# heartEM.net
KiCad netlist of a schematic drawn in EAGLE
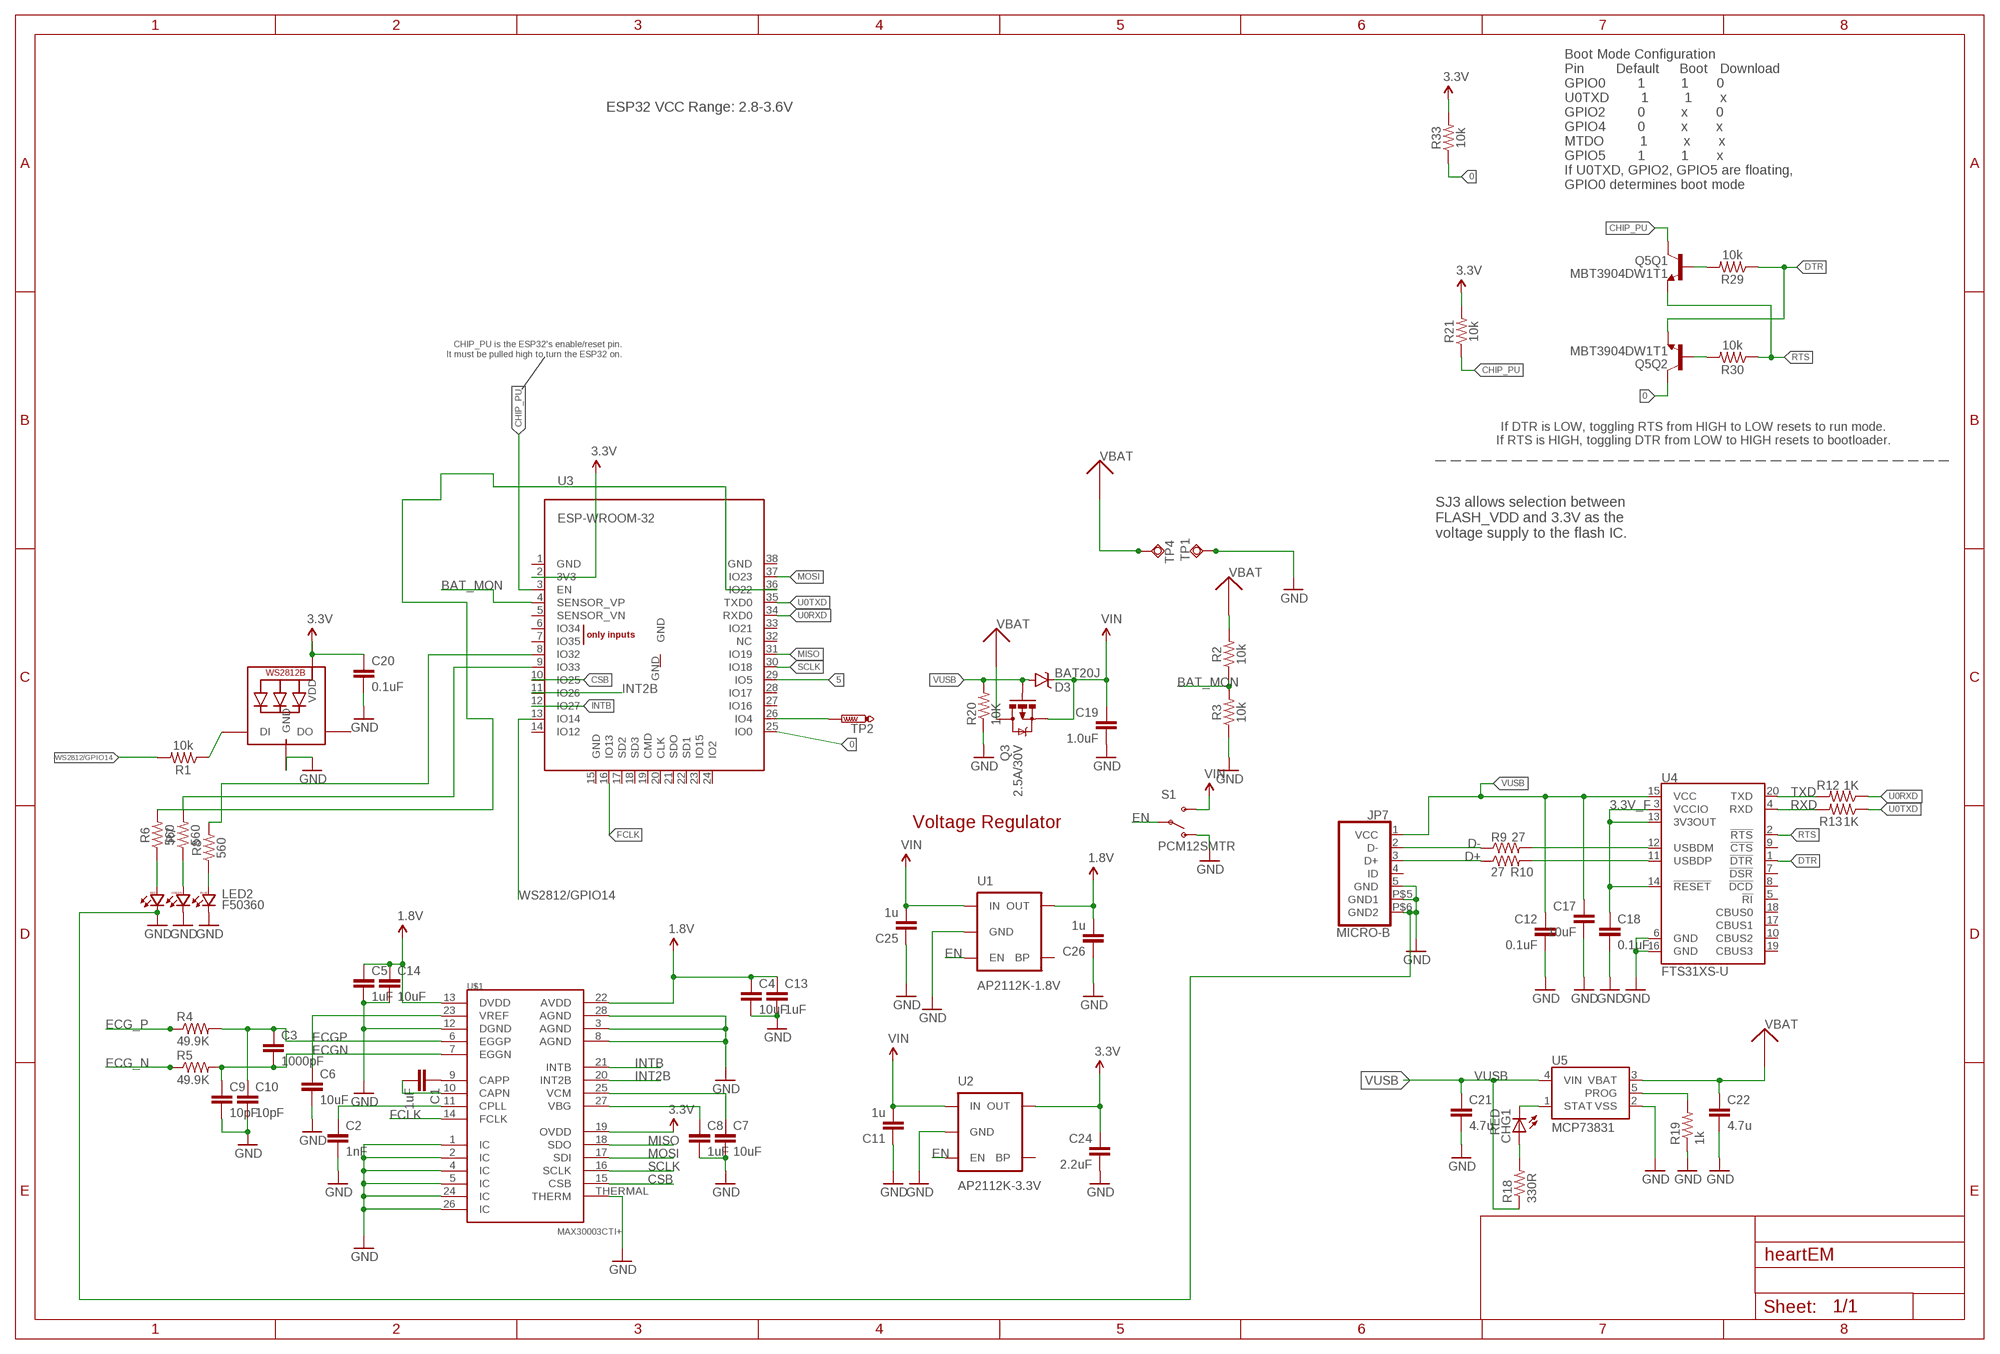
[diagram p0: schematic, sheet 1]

(export (version "E")
  (design (tool "Eeschema 10.0.6"))
  (components
    (comp (ref "C1")
      (value "1uF")
      (footprint "eagle-import:C0603")
      (libsource (lib "eagle-import") (part "C-EUC0603"))
    )
    (comp (ref "C2")
      (value "1nF")
      (footprint "eagle-import:C0603")
      (libsource (lib "eagle-import") (part "C-EUC0603"))
    )
    (comp (ref "C3")
      (value "1000pF")
      (footprint "eagle-import:C0402")
      (libsource (lib "eagle-import") (part "C-EUC0402"))
    )
    (comp (ref "C4")
      (value "10uF")
      (footprint "eagle-import:C0805")
      (libsource (lib "eagle-import") (part "C-EUC0805"))
    )
    (comp (ref "C5")
      (value "1uF")
      (footprint "eagle-import:C0402")
      (libsource (lib "eagle-import") (part "C-EUC0402"))
    )
    (comp (ref "C6")
      (value "10uF")
      (footprint "eagle-import:C0805")
      (libsource (lib "eagle-import") (part "C-EUC0805"))
    )
    (comp (ref "C7")
      (value "10uF")
      (footprint "eagle-import:C0805")
      (libsource (lib "eagle-import") (part "C-EUC0805"))
    )
    (comp (ref "C8")
      (value "1uF")
      (footprint "eagle-import:C0805")
      (libsource (lib "eagle-import") (part "C-EUC0805"))
    )
    (comp (ref "C9")
      (value "10pF")
      (footprint "eagle-import:C0402")
      (libsource (lib "eagle-import") (part "C-EUC0402"))
    )
    (comp (ref "C10")
      (value "10pF")
      (footprint "eagle-import:C0402")
      (libsource (lib "eagle-import") (part "C-EUC0402"))
    )
    (comp (ref "C11")
      (value "1u")
      (footprint "eagle-import:C0402")
      (libsource (lib "eagle-import") (part "C-EUC0402"))
    )
    (comp (ref "C12")
      (value "0.1uF")
      (footprint "eagle-import:C0402")
      (libsource (lib "eagle-import") (part "C-EUC0402"))
    )
    (comp (ref "C13")
      (value "1uF")
      (footprint "eagle-import:C0805")
      (libsource (lib "eagle-import") (part "C-EUC0805"))
    )
    (comp (ref "C14")
      (value "10uF")
      (footprint "eagle-import:C0603")
      (libsource (lib "eagle-import") (part "C-EUC0603"))
    )
    (comp (ref "C17")
      (value "10uF")
      (footprint "eagle-import:C0805")
      (libsource (lib "eagle-import") (part "C-EUC0805"))
    )
    (comp (ref "C18")
      (value "0.1uF")
      (footprint "eagle-import:C0402")
      (libsource (lib "eagle-import") (part "C-EUC0402"))
    )
    (comp (ref "C19")
      (value "1.0uF")
      (footprint "eagle-import:C0402")
      (libsource (lib "eagle-import") (part "C-EUC0402"))
    )
    (comp (ref "C20")
      (value "0.1uF")
      (footprint "eagle-import:0603")
      (libsource (lib "eagle-import") (part "0.1UF-0603-25V-(+80/-20%)"))
    )
    (comp (ref "C21")
      (value "4.7u")
      (footprint "eagle-import:C0805")
      (libsource (lib "eagle-import") (part "C-EUC0805"))
    )
    (comp (ref "C22")
      (value "4.7u")
      (footprint "eagle-import:C0805")
      (libsource (lib "eagle-import") (part "C-EUC0805"))
    )
    (comp (ref "C24")
      (value "2.2uF")
      (footprint "eagle-import:C0603")
      (libsource (lib "eagle-import") (part "C-EUC0603"))
    )
    (comp (ref "C25")
      (value "1u")
      (footprint "eagle-import:C0402")
      (libsource (lib "eagle-import") (part "C-EUC0402"))
    )
    (comp (ref "C26")
      (value "1u")
      (footprint "eagle-import:C0402")
      (libsource (lib "eagle-import") (part "C-EUC0402"))
    )
    (comp (ref "CHG1")
      (value "RED")
      (footprint "eagle-import:CHIPLED_0603")
      (libsource (lib "eagle-import") (part "LEDCHIPLED_0603"))
    )
    (comp (ref "D3")
      (value "BAT20J")
      (footprint "eagle-import:SOD-323")
      (libsource (lib "eagle-import") (part "DIODE-SCHOTTKY-BAT20J"))
    )
    (comp (ref "JP7")
      (value "MICRO-B")
      (footprint "eagle-import:MICRO-B")
      (libsource (lib "eagle-import") (part "MICRO-B"))
    )
    (comp (ref "LED1")
      (value "WS2812B5050")
      (footprint "eagle-import:WS2812B")
      (libsource (lib "eagle-import") (part "WS2812B5050"))
    )
    (comp (ref "LED2")
      (value "F50360")
      (footprint "eagle-import:F50360")
      (libsource (lib "eagle-import") (part "F50360"))
    )
    (comp (ref "Q3")
      (value "2.5A/30V")
      (footprint "eagle-import:SOT23-3")
      (libsource (lib "eagle-import") (part "MOSFET-PCHANNELDMG2307L"))
    )
    (comp (ref "Q5")
      (value "MBT3904DW1T1")
      (footprint "eagle-import:SC70-6")
      (libsource (lib "eagle-import") (part "MBT3904DW1T1"))
    )
    (comp (ref "R1")
      (value "10k")
      (footprint "eagle-import:0603")
      (libsource (lib "eagle-import") (part "10KOHM-1/10W-1%(0603)0603"))
    )
    (comp (ref "R2")
      (value "10k")
      (footprint "eagle-import:0603")
      (libsource (lib "eagle-import") (part "10KOHM-1/10W-1%(0603)0603"))
    )
    (comp (ref "R3")
      (value "10k")
      (footprint "eagle-import:0603")
      (libsource (lib "eagle-import") (part "10KOHM-1/10W-1%(0603)0603"))
    )
    (comp (ref "R4")
      (value "49.9K")
      (footprint "eagle-import:0805")
      (libsource (lib "eagle-import") (part "RESISTOR0805-RES"))
    )
    (comp (ref "R5")
      (value "49.9K")
      (footprint "eagle-import:0805")
      (libsource (lib "eagle-import") (part "RESISTOR0805-RES"))
    )
    (comp (ref "R6")
      (value "560")
      (footprint "eagle-import:0603")
      (libsource (lib "eagle-import") (part "10KOHM-1/10W-1%(0603)0603"))
    )
    (comp (ref "R7")
      (value "560")
      (footprint "eagle-import:0603")
      (libsource (lib "eagle-import") (part "10KOHM-1/10W-1%(0603)0603"))
    )
    (comp (ref "R8")
      (value "560")
      (footprint "eagle-import:0603")
      (libsource (lib "eagle-import") (part "10KOHM-1/10W-1%(0603)0603"))
    )
    (comp (ref "R9")
      (value "27")
      (footprint "eagle-import:R0402")
      (libsource (lib "eagle-import") (part "R-US_R0402"))
    )
    (comp (ref "R10")
      (value "27")
      (footprint "eagle-import:R0402")
      (libsource (lib "eagle-import") (part "R-US_R0402"))
    )
    (comp (ref "R12")
      (value "1K")
      (footprint "eagle-import:R0402")
      (libsource (lib "eagle-import") (part "R-US_R0402"))
    )
    (comp (ref "R13")
      (value "1K")
      (footprint "eagle-import:R0402")
      (libsource (lib "eagle-import") (part "R-US_R0402"))
    )
    (comp (ref "R18")
      (value "330R")
      (footprint "eagle-import:R0402")
      (libsource (lib "eagle-import") (part "R-US_R0402"))
    )
    (comp (ref "R19")
      (value "1k")
      (footprint "eagle-import:R0402")
      (libsource (lib "eagle-import") (part "R-US_R0402"))
    )
    (comp (ref "R20")
      (value "10K")
      (footprint "eagle-import:R0402")
      (libsource (lib "eagle-import") (part "R-US_R0402"))
    )
    (comp (ref "R21")
      (value "10k")
      (footprint "eagle-import:0603")
      (libsource (lib "eagle-import") (part "10KOHM-1/10W-1%(0603)0603"))
    )
    (comp (ref "R29")
      (value "10k")
      (footprint "eagle-import:0603")
      (libsource (lib "eagle-import") (part "10KOHM-0603-1/10W-1%"))
    )
    (comp (ref "R30")
      (value "10k")
      (footprint "eagle-import:0603")
      (libsource (lib "eagle-import") (part "10KOHM-0603-1/10W-1%"))
    )
    (comp (ref "R33")
      (value "10k")
      (footprint "eagle-import:0603")
      (libsource (lib "eagle-import") (part "10KOHM-1/10W-1%(0603)0603"))
    )
    (comp (ref "S1")
      (value "PCM12SMTR")
      (footprint "eagle-import:SWITCH-SPST-SMD-A")
      (libsource (lib "eagle-import") (part "SWITCH-SPDT-SMD-A"))
    )
    (comp (ref "TP1")
      (value "TPSQTP20SQ")
      (footprint "eagle-import:TP20SQ")
      (libsource (lib "eagle-import") (part "TPSQTP20SQ"))
    )
    (comp (ref "TP2")
      (value "PTR1TP10SQ")
      (footprint "eagle-import:TP10SQ")
      (libsource (lib "eagle-import") (part "PTR1TP10SQ"))
    )
    (comp (ref "TP4")
      (value "TPSQTP20SQ")
      (footprint "eagle-import:TP20SQ")
      (libsource (lib "eagle-import") (part "TPSQTP20SQ"))
    )
    (comp (ref "U$1")
      (value "MAX30003CTI+")
      (footprint "eagle-import:QFN-28")
      (libsource (lib "eagle-import") (part "MAX30003"))
    )
    (comp (ref "U1")
      (value "AP2112K-1.8V")
      (footprint "eagle-import:SOT23-5")
      (libsource (lib "eagle-import") (part "V_REG_LDOSMD"))
    )
    (comp (ref "U2")
      (value "AP2112K-3.3V")
      (footprint "eagle-import:SOT23-5")
      (libsource (lib "eagle-import") (part "V_REG_LDOSMD"))
    )
    (comp (ref "U3")
      (value "ESP-WROOM-32")
      (footprint "eagle-import:ESP-WROOM-32")
      (fields (field (name "SPICEPREFIX") "X"))
      (libsource (lib "eagle-import") (part "ESP-WROOM-32"))
    )
    (comp (ref "U4")
      (value "FTS31XS-U")
      (footprint "eagle-import:SSOP20_L")
      (libsource (lib "eagle-import") (part "FT231XS"))
    )
    (comp (ref "U5")
      (value "MCP73831")
      (footprint "eagle-import:SOT23-5")
      (libsource (lib "eagle-import") (part "MCP73831"))
    )
  )
  (nets
    (net (code "1") (name "/3.3V_F") (class "Default")
      (node (ref "C18") (pin "1") (pinfunction "1_1") (pintype "passive"))
      (node (ref "U4") (pin "13") (pinfunction "3V3OUT_13") (pintype "bidirectional"))
      (node (ref "U4") (pin "14") (pinfunction "~{RESET}_14") (pintype "bidirectional"))
      (node (ref "U4") (pin "3") (pinfunction "VCCIO_3") (pintype "bidirectional"))
    )
    (net (code "2") (name "/BAT_MON") (class "Default")
      (node (ref "R2") (pin "1") (pinfunction "1_1") (pintype "passive"))
      (node (ref "R3") (pin "2") (pinfunction "2_2") (pintype "passive"))
      (node (ref "U3") (pin "4") (pinfunction "SENSOR_VP_4") (pintype "input"))
    )
    (net (code "3") (name "/D+") (class "Default")
      (node (ref "JP7") (pin "3") (pinfunction "D+_3") (pintype "bidirectional"))
      (node (ref "R10") (pin "1") (pinfunction "1_1") (pintype "passive"))
    )
    (net (code "4") (name "/D-") (class "Default")
      (node (ref "JP7") (pin "2") (pinfunction "D-_2") (pintype "bidirectional"))
      (node (ref "R9") (pin "1") (pinfunction "1_1") (pintype "passive"))
    )
    (net (code "5") (name "/ECGN") (class "Default")
      (node (ref "C3") (pin "2") (pinfunction "2_2") (pintype "passive"))
      (node (ref "C9") (pin "1") (pinfunction "1_1") (pintype "passive"))
      (node (ref "R5") (pin "2") (pinfunction "2_2") (pintype "passive"))
      (node (ref "U$1") (pin "7") (pinfunction "EGGN_7") (pintype "bidirectional"))
    )
    (net (code "6") (name "/ECGP") (class "Default")
      (node (ref "C10") (pin "1") (pinfunction "1_1") (pintype "passive"))
      (node (ref "C3") (pin "1") (pinfunction "1_1") (pintype "passive"))
      (node (ref "R4") (pin "2") (pinfunction "2_2") (pintype "passive"))
      (node (ref "U$1") (pin "6") (pinfunction "EGGP_6") (pintype "bidirectional"))
    )
    (net (code "7") (name "/ECG_N") (class "Default")
      (node (ref "R5") (pin "1") (pinfunction "1_1") (pintype "passive"))
    )
    (net (code "8") (name "/ECG_P") (class "Default")
      (node (ref "R4") (pin "1") (pinfunction "1_1") (pintype "passive"))
    )
    (net (code "9") (name "/EN") (class "Default")
      (node (ref "S1") (pin "2") (pinfunction "P_2") (pintype "passive"))
      (node (ref "U1") (pin "3") (pinfunction "EN_3") (pintype "input"))
      (node (ref "U2") (pin "3") (pinfunction "EN_3") (pintype "input"))
    )
    (net (code "10") (name "/INT2B") (class "Default")
      (node (ref "U$1") (pin "20") (pinfunction "INT2B_20") (pintype "bidirectional"))
      (node (ref "U3") (pin "11") (pinfunction "IO26_11") (pintype "bidirectional"))
    )
    (net (code "11") (name "/RXD") (class "Default")
      (node (ref "R13") (pin "2") (pinfunction "2_2") (pintype "passive"))
      (node (ref "U4") (pin "4") (pinfunction "RXD_4") (pintype "bidirectional"))
    )
    (net (code "12") (name "/TXD") (class "Default")
      (node (ref "R12") (pin "2") (pinfunction "2_2") (pintype "passive"))
      (node (ref "U4") (pin "20") (pinfunction "TXD_20") (pintype "bidirectional"))
    )
    (net (code "13") (name "0") (class "Default")
      (node (ref "Q5") (pin "6") (pinfunction "C_6") (pintype "passive"))
      (node (ref "R33") (pin "1") (pinfunction "1_1") (pintype "passive"))
      (node (ref "U3") (pin "25") (pinfunction "IO0_25") (pintype "bidirectional"))
    )
    (net (code "14") (name "1.8V") (class "Default")
      (node (ref "C13") (pin "1") (pinfunction "1_1") (pintype "passive"))
      (node (ref "C14") (pin "1") (pinfunction "1_1") (pintype "passive"))
      (node (ref "C26") (pin "2") (pinfunction "2_2") (pintype "passive"))
      (node (ref "C4") (pin "1") (pinfunction "1_1") (pintype "passive"))
      (node (ref "C5") (pin "1") (pinfunction "1_1") (pintype "passive"))
      (node (ref "U$1") (pin "13") (pinfunction "DVDD_13") (pintype "bidirectional"))
      (node (ref "U$1") (pin "22") (pinfunction "AVDD_22") (pintype "bidirectional"))
      (node (ref "U1") (pin "5") (pinfunction "OUT_5") (pintype "passive"))
    )
    (net (code "15") (name "3.3V") (class "Default")
      (node (ref "C20") (pin "1") (pinfunction "1_1") (pintype "passive"))
      (node (ref "C24") (pin "1") (pinfunction "1_1") (pintype "passive"))
      (node (ref "LED1") (pin "1-VDD") (pinfunction "VDD_1-VDD") (pintype "power_in"))
      (node (ref "R21") (pin "2") (pinfunction "2_2") (pintype "passive"))
      (node (ref "R33") (pin "2") (pinfunction "2_2") (pintype "passive"))
      (node (ref "U$1") (pin "19") (pinfunction "OVDD_19") (pintype "bidirectional"))
      (node (ref "U2") (pin "5") (pinfunction "OUT_5") (pintype "passive"))
      (node (ref "U3") (pin "2") (pinfunction "3V3_2") (pintype "bidirectional"))
    )
    (net (code "16") (name "5") (class "Default")
      (node (ref "U3") (pin "29") (pinfunction "IO5_29") (pintype "bidirectional"))
    )
    (net (code "17") (name "CHIP_PU") (class "Default")
      (node (ref "Q5") (pin "3") (pinfunction "C_3") (pintype "passive"))
      (node (ref "R21") (pin "1") (pinfunction "1_1") (pintype "passive"))
      (node (ref "U3") (pin "3") (pinfunction "EN_3") (pintype "bidirectional"))
    )
    (net (code "18") (name "CSB") (class "Default")
      (node (ref "U$1") (pin "15") (pinfunction "CSB_15") (pintype "bidirectional"))
      (node (ref "U3") (pin "10") (pinfunction "IO25_10") (pintype "bidirectional"))
    )
    (net (code "19") (name "DTR") (class "Default")
      (node (ref "Q5") (pin "1") (pinfunction "E_1") (pintype "passive"))
      (node (ref "R29") (pin "1") (pinfunction "1_1") (pintype "passive"))
      (node (ref "U4") (pin "1") (pinfunction "~{DTR}_1") (pintype "bidirectional"))
    )
    (net (code "20") (name "FCLK") (class "Default")
      (node (ref "U$1") (pin "14") (pinfunction "FCLK_14") (pintype "bidirectional"))
      (node (ref "U3") (pin "16") (pinfunction "IO13_16") (pintype "bidirectional"))
    )
    (net (code "21") (name "GND") (class "Default")
      (node (ref "C10") (pin "2") (pinfunction "2_2") (pintype "passive"))
      (node (ref "C11") (pin "1") (pinfunction "1_1") (pintype "passive"))
      (node (ref "C12") (pin "2") (pinfunction "2_2") (pintype "passive"))
      (node (ref "C13") (pin "2") (pinfunction "2_2") (pintype "passive"))
      (node (ref "C14") (pin "2") (pinfunction "2_2") (pintype "passive"))
      (node (ref "C17") (pin "2") (pinfunction "2_2") (pintype "passive"))
      (node (ref "C18") (pin "2") (pinfunction "2_2") (pintype "passive"))
      (node (ref "C19") (pin "2") (pinfunction "2_2") (pintype "passive"))
      (node (ref "C2") (pin "2") (pinfunction "2_2") (pintype "passive"))
      (node (ref "C20") (pin "2") (pinfunction "2_2") (pintype "passive"))
      (node (ref "C21") (pin "2") (pinfunction "2_2") (pintype "passive"))
      (node (ref "C22") (pin "2") (pinfunction "2_2") (pintype "passive"))
      (node (ref "C24") (pin "2") (pinfunction "2_2") (pintype "passive"))
      (node (ref "C25") (pin "1") (pinfunction "1_1") (pintype "passive"))
      (node (ref "C26") (pin "1") (pinfunction "1_1") (pintype "passive"))
      (node (ref "C4") (pin "2") (pinfunction "2_2") (pintype "passive"))
      (node (ref "C5") (pin "2") (pinfunction "2_2") (pintype "passive"))
      (node (ref "C6") (pin "2") (pinfunction "2_2") (pintype "passive"))
      (node (ref "C7") (pin "2") (pinfunction "2_2") (pintype "passive"))
      (node (ref "C8") (pin "2") (pinfunction "2_2") (pintype "passive"))
      (node (ref "C9") (pin "2") (pinfunction "2_2") (pintype "passive"))
      (node (ref "JP7") (pin "5") (pinfunction "GND_5") (pintype "bidirectional"))
      (node (ref "JP7") (pin "P$5") (pinfunction "GND1_P$5") (pintype "bidirectional"))
      (node (ref "JP7") (pin "P$6") (pinfunction "GND2_P$6") (pintype "bidirectional"))
      (node (ref "LED1") (pin "3-GND") (pinfunction "GND_3-GND") (pintype "power_in"))
      (node (ref "LED2") (pin "BC") (pinfunction "BC_BC") (pintype "passive"))
      (node (ref "LED2") (pin "GC") (pinfunction "GC_GC") (pintype "passive"))
      (node (ref "LED2") (pin "RC") (pinfunction "RC_RC") (pintype "passive"))
      (node (ref "R19") (pin "1") (pinfunction "1_1") (pintype "passive"))
      (node (ref "R20") (pin "1") (pinfunction "1_1") (pintype "passive"))
      (node (ref "R3") (pin "1") (pinfunction "1_1") (pintype "passive"))
      (node (ref "S1") (pin "1") (pinfunction "O_1") (pintype "passive"))
      (node (ref "TP1") (pin "TP") (pinfunction "TP_TP") (pintype "input"))
      (node (ref "U$1") (pin "1") (pinfunction "IC_1") (pintype "bidirectional"))
      (node (ref "U$1") (pin "12") (pinfunction "DGND_12") (pintype "bidirectional"))
      (node (ref "U$1") (pin "2") (pinfunction "IC_2") (pintype "bidirectional"))
      (node (ref "U$1") (pin "24") (pinfunction "IC_24") (pintype "bidirectional"))
      (node (ref "U$1") (pin "26") (pinfunction "IC_26") (pintype "bidirectional"))
      (node (ref "U$1") (pin "28") (pinfunction "AGND_28") (pintype "bidirectional"))
      (node (ref "U$1") (pin "3") (pinfunction "AGND_3") (pintype "bidirectional"))
      (node (ref "U$1") (pin "4") (pinfunction "IC_4") (pintype "bidirectional"))
      (node (ref "U$1") (pin "5") (pinfunction "IC_5") (pintype "bidirectional"))
      (node (ref "U$1") (pin "8") (pinfunction "AGND_8") (pintype "bidirectional"))
      (node (ref "U$1") (pin "THERMAL") (pinfunction "THERM_THERMAL") (pintype "bidirectional"))
      (node (ref "U1") (pin "2") (pinfunction "GND_2") (pintype "input"))
      (node (ref "U2") (pin "2") (pinfunction "GND_2") (pintype "input"))
      (node (ref "U4") (pin "16") (pinfunction "GND_16") (pintype "bidirectional"))
      (node (ref "U4") (pin "6") (pinfunction "GND_6") (pintype "bidirectional"))
      (node (ref "U5") (pin "2") (pinfunction "VSS_2") (pintype "power_in"))
    )
    (net (code "22") (name "INTB") (class "Default")
      (node (ref "U$1") (pin "21") (pinfunction "INTB_21") (pintype "bidirectional"))
      (node (ref "U3") (pin "12") (pinfunction "IO27_12") (pintype "bidirectional"))
    )
    (net (code "23") (name "MISO") (class "Default")
      (node (ref "U$1") (pin "18") (pinfunction "SDO_18") (pintype "bidirectional"))
      (node (ref "U3") (pin "31") (pinfunction "IO19_31") (pintype "bidirectional"))
    )
    (net (code "24") (name "MOSI") (class "Default")
      (node (ref "U$1") (pin "17") (pinfunction "SDI_17") (pintype "bidirectional"))
      (node (ref "U3") (pin "37") (pinfunction "IO23_37") (pintype "bidirectional"))
    )
    (net (code "25") (name "Net-(CHG1-PadA)") (class "Default")
      (node (ref "CHG1") (pin "A") (pinfunction "A_A") (pintype "passive"))
      (node (ref "R18") (pin "2") (pinfunction "2_2") (pintype "passive"))
    )
    (net (code "26") (name "Net-(LED1-DI)") (class "Default")
      (node (ref "LED1") (pin "4-DIN") (pinfunction "DI_4-DIN") (pintype "input"))
      (node (ref "R1") (pin "1") (pinfunction "1_1") (pintype "passive"))
    )
    (net (code "27") (name "Net-(LED2-PadBA)") (class "Default")
      (node (ref "LED2") (pin "BA") (pinfunction "BA_BA") (pintype "passive"))
      (node (ref "R8") (pin "1") (pinfunction "1_1") (pintype "passive"))
    )
    (net (code "28") (name "Net-(LED2-PadGA)") (class "Default")
      (node (ref "LED2") (pin "GA") (pinfunction "GA_GA") (pintype "passive"))
      (node (ref "R7") (pin "1") (pinfunction "1_1") (pintype "passive"))
    )
    (net (code "29") (name "Net-(LED2-PadRA)") (class "Default")
      (node (ref "LED2") (pin "RA") (pinfunction "RA_RA") (pintype "passive"))
      (node (ref "R6") (pin "1") (pinfunction "1_1") (pintype "passive"))
    )
    (net (code "30") (name "Net-(Q5A-B)") (class "Default")
      (node (ref "Q5") (pin "5") (pinfunction "B_5") (pintype "passive"))
      (node (ref "R29") (pin "2") (pinfunction "2_2") (pintype "passive"))
    )
    (net (code "31") (name "Net-(Q5B-B)") (class "Default")
      (node (ref "Q5") (pin "2") (pinfunction "B_2") (pintype "passive"))
      (node (ref "R30") (pin "2") (pinfunction "2_2") (pintype "passive"))
    )
    (net (code "32") (name "Net-(U$1-CAPN)") (class "Default")
      (node (ref "C1") (pin "2") (pinfunction "2_2") (pintype "passive"))
      (node (ref "U$1") (pin "10") (pinfunction "CAPN_10") (pintype "bidirectional"))
    )
    (net (code "33") (name "Net-(U$1-CAPP)") (class "Default")
      (node (ref "C1") (pin "1") (pinfunction "1_1") (pintype "passive"))
      (node (ref "U$1") (pin "9") (pinfunction "CAPP_9") (pintype "bidirectional"))
    )
    (net (code "34") (name "Net-(U$1-CPLL)") (class "Default")
      (node (ref "C2") (pin "1") (pinfunction "1_1") (pintype "passive"))
      (node (ref "U$1") (pin "11") (pinfunction "CPLL_11") (pintype "bidirectional"))
    )
    (net (code "35") (name "Net-(U$1-VBG)") (class "Default")
      (node (ref "C8") (pin "1") (pinfunction "1_1") (pintype "passive"))
      (node (ref "U$1") (pin "27") (pinfunction "VBG_27") (pintype "bidirectional"))
    )
    (net (code "36") (name "Net-(U$1-VCM)") (class "Default")
      (node (ref "C7") (pin "1") (pinfunction "1_1") (pintype "passive"))
      (node (ref "U$1") (pin "25") (pinfunction "VCM_25") (pintype "bidirectional"))
    )
    (net (code "37") (name "Net-(U$1-VREF)") (class "Default")
      (node (ref "C6") (pin "1") (pinfunction "1_1") (pintype "passive"))
      (node (ref "U$1") (pin "23") (pinfunction "VREF_23") (pintype "bidirectional"))
    )
    (net (code "38") (name "Net-(U3-IO4)") (class "Default")
      (node (ref "TP2") (pin "TP") (pinfunction "TP_TP") (pintype "input"))
      (node (ref "U3") (pin "26") (pinfunction "IO4_26") (pintype "bidirectional"))
    )
    (net (code "39") (name "Net-(U3-IO22)") (class "Default")
      (node (ref "R6") (pin "2") (pinfunction "2_2") (pintype "passive"))
      (node (ref "U3") (pin "36") (pinfunction "IO22_36") (pintype "bidirectional"))
    )
    (net (code "40") (name "Net-(U3-IO32)") (class "Default")
      (node (ref "R8") (pin "2") (pinfunction "2_2") (pintype "passive"))
      (node (ref "U3") (pin "8") (pinfunction "IO32_8") (pintype "bidirectional"))
    )
    (net (code "41") (name "Net-(U3-IO33)") (class "Default")
      (node (ref "R7") (pin "2") (pinfunction "2_2") (pintype "passive"))
      (node (ref "U3") (pin "9") (pinfunction "IO33_9") (pintype "bidirectional"))
    )
    (net (code "42") (name "Net-(U4-USBDM)") (class "Default")
      (node (ref "R9") (pin "2") (pinfunction "2_2") (pintype "passive"))
      (node (ref "U4") (pin "12") (pinfunction "USBDM_12") (pintype "bidirectional"))
    )
    (net (code "43") (name "Net-(U4-USBDP)") (class "Default")
      (node (ref "R10") (pin "2") (pinfunction "2_2") (pintype "passive"))
      (node (ref "U4") (pin "11") (pinfunction "USBDP_11") (pintype "bidirectional"))
    )
    (net (code "44") (name "Net-(U5-PROG)") (class "Default")
      (node (ref "R19") (pin "2") (pinfunction "2_2") (pintype "passive"))
      (node (ref "U5") (pin "5") (pinfunction "PROG_5") (pintype "input"))
    )
    (net (code "45") (name "Net-(U5-STAT)") (class "Default")
      (node (ref "CHG1") (pin "C") (pinfunction "C_C") (pintype "passive"))
      (node (ref "U5") (pin "1") (pinfunction "STAT_1") (pintype "output"))
    )
    (net (code "46") (name "RTS") (class "Default")
      (node (ref "Q5") (pin "4") (pinfunction "E_4") (pintype "passive"))
      (node (ref "R30") (pin "1") (pinfunction "1_1") (pintype "passive"))
      (node (ref "U4") (pin "2") (pinfunction "~{RTS}_2") (pintype "bidirectional"))
    )
    (net (code "47") (name "SCLK") (class "Default")
      (node (ref "U$1") (pin "16") (pinfunction "SCLK_16") (pintype "bidirectional"))
      (node (ref "U3") (pin "30") (pinfunction "IO18_30") (pintype "bidirectional"))
    )
    (net (code "48") (name "U0RXD") (class "Default")
      (node (ref "R12") (pin "1") (pinfunction "1_1") (pintype "passive"))
      (node (ref "U3") (pin "34") (pinfunction "RXD0_34") (pintype "bidirectional"))
    )
    (net (code "49") (name "U0TXD") (class "Default")
      (node (ref "R13") (pin "1") (pinfunction "1_1") (pintype "passive"))
      (node (ref "U3") (pin "35") (pinfunction "TXD0_35") (pintype "bidirectional"))
    )
    (net (code "50") (name "VBAT") (class "Default")
      (node (ref "C22") (pin "1") (pinfunction "1_1") (pintype "passive"))
      (node (ref "Q3") (pin "3") (pinfunction "D_3") (pintype "passive"))
      (node (ref "R2") (pin "2") (pinfunction "2_2") (pintype "passive"))
      (node (ref "TP4") (pin "TP") (pinfunction "TP_TP") (pintype "input"))
      (node (ref "U5") (pin "3") (pinfunction "VBAT_3") (pintype "power_in"))
    )
    (net (code "51") (name "VIN") (class "Default")
      (node (ref "C11") (pin "2") (pinfunction "2_2") (pintype "passive"))
      (node (ref "C19") (pin "1") (pinfunction "1_1") (pintype "passive"))
      (node (ref "C25") (pin "2") (pinfunction "2_2") (pintype "passive"))
      (node (ref "D3") (pin "C") (pinfunction "C_C") (pintype "passive"))
      (node (ref "Q3") (pin "2") (pinfunction "S_2") (pintype "passive"))
      (node (ref "S1") (pin "3") (pinfunction "S_3") (pintype "passive"))
      (node (ref "U1") (pin "1") (pinfunction "IN_1") (pintype "input"))
      (node (ref "U2") (pin "1") (pinfunction "IN_1") (pintype "input"))
    )
    (net (code "52") (name "VUSB") (class "Default")
      (node (ref "C12") (pin "1") (pinfunction "1_1") (pintype "passive"))
      (node (ref "C17") (pin "1") (pinfunction "1_1") (pintype "passive"))
      (node (ref "C21") (pin "1") (pinfunction "1_1") (pintype "passive"))
      (node (ref "D3") (pin "A") (pinfunction "A_A") (pintype "passive"))
      (node (ref "JP7") (pin "1") (pinfunction "VCC_1") (pintype "bidirectional"))
      (node (ref "Q3") (pin "1") (pinfunction "G_1") (pintype "passive"))
      (node (ref "R18") (pin "1") (pinfunction "1_1") (pintype "passive"))
      (node (ref "R20") (pin "2") (pinfunction "2_2") (pintype "passive"))
      (node (ref "U4") (pin "15") (pinfunction "VCC_15") (pintype "bidirectional"))
      (node (ref "U5") (pin "4") (pinfunction "VIN_4") (pintype "power_in"))
    )
    (net (code "53") (name "WS2812{slash}GPIO14") (class "Default")
      (node (ref "R1") (pin "2") (pinfunction "2_2") (pintype "passive"))
      (node (ref "U3") (pin "13") (pinfunction "IO14_13") (pintype "bidirectional"))
    )
    (net (code "54") (name "unconnected-(JP7-ID-Pad4)") (class "Default")
      (node (ref "JP7") (pin "4") (pinfunction "ID_4") (pintype "bidirectional"))
    )
    (net (code "55") (name "unconnected-(LED1-DO-Pad2-DOUT)") (class "Default")
      (node (ref "LED1") (pin "2-DOUT") (pinfunction "DO_2-DOUT") (pintype "output"))
    )
    (net (code "56") (name "unconnected-(U1-BP-Pad4)") (class "Default")
      (node (ref "U1") (pin "4") (pinfunction "BP_4") (pintype "input"))
    )
    (net (code "57") (name "unconnected-(U2-BP-Pad4)") (class "Default")
      (node (ref "U2") (pin "4") (pinfunction "BP_4") (pintype "input"))
    )
    (net (code "58") (name "unconnected-(U3-CLK-Pad20)") (class "Default")
      (node (ref "U3") (pin "20") (pinfunction "CLK_20") (pintype "bidirectional"))
    )
    (net (code "59") (name "unconnected-(U3-CMD-Pad19)") (class "Default")
      (node (ref "U3") (pin "19") (pinfunction "CMD_19") (pintype "bidirectional"))
    )
    (net (code "60") (name "unconnected-(U3-GND-Pad1)") (class "Default")
      (node (ref "U3") (pin "1") (pinfunction "GND_1") (pintype "bidirectional"))
    )
    (net (code "61") (name "unconnected-(U3-GND-Pad15)") (class "Default")
      (node (ref "U3") (pin "15") (pinfunction "GND_15") (pintype "bidirectional"))
    )
    (net (code "62") (name "unconnected-(U3-GND-Pad38)") (class "Default")
      (node (ref "U3") (pin "38") (pinfunction "GND_38") (pintype "bidirectional"))
    )
    (net (code "63") (name "unconnected-(U3-IO2-Pad24)") (class "Default")
      (node (ref "U3") (pin "24") (pinfunction "IO2_24") (pintype "bidirectional"))
    )
    (net (code "64") (name "unconnected-(U3-IO12-Pad14)") (class "Default")
      (node (ref "U3") (pin "14") (pinfunction "IO12_14") (pintype "bidirectional"))
    )
    (net (code "65") (name "unconnected-(U3-IO15-Pad23)") (class "Default")
      (node (ref "U3") (pin "23") (pinfunction "IO15_23") (pintype "bidirectional"))
    )
    (net (code "66") (name "unconnected-(U3-IO16-Pad27)") (class "Default")
      (node (ref "U3") (pin "27") (pinfunction "IO16_27") (pintype "bidirectional"))
    )
    (net (code "67") (name "unconnected-(U3-IO17-Pad28)") (class "Default")
      (node (ref "U3") (pin "28") (pinfunction "IO17_28") (pintype "bidirectional"))
    )
    (net (code "68") (name "unconnected-(U3-IO21-Pad33)") (class "Default")
      (node (ref "U3") (pin "33") (pinfunction "IO21_33") (pintype "bidirectional"))
    )
    (net (code "69") (name "unconnected-(U3-IO34-Pad6)") (class "Default")
      (node (ref "U3") (pin "6") (pinfunction "IO34_6") (pintype "input"))
    )
    (net (code "70") (name "unconnected-(U3-IO35-Pad7)") (class "Default")
      (node (ref "U3") (pin "7") (pinfunction "IO35_7") (pintype "input"))
    )
    (net (code "71") (name "unconnected-(U3-NC-Pad32)") (class "Default")
      (node (ref "U3") (pin "32") (pinfunction "NC_32") (pintype "bidirectional"))
    )
    (net (code "72") (name "unconnected-(U3-PadGND)") (class "Default")
      (node (ref "U3") (pin "GND") (pinfunction "GND_GND") (pintype "bidirectional"))
    )
    (net (code "73") (name "unconnected-(U3-SD1-Pad22)") (class "Default")
      (node (ref "U3") (pin "22") (pinfunction "SD1_22") (pintype "bidirectional"))
    )
    (net (code "74") (name "unconnected-(U3-SD2-Pad17)") (class "Default")
      (node (ref "U3") (pin "17") (pinfunction "SD2_17") (pintype "bidirectional"))
    )
    (net (code "75") (name "unconnected-(U3-SD3-Pad18)") (class "Default")
      (node (ref "U3") (pin "18") (pinfunction "SD3_18") (pintype "bidirectional"))
    )
    (net (code "76") (name "unconnected-(U3-SDO-Pad21)") (class "Default")
      (node (ref "U3") (pin "21") (pinfunction "SDO_21") (pintype "bidirectional"))
    )
    (net (code "77") (name "unconnected-(U3-SENSOR_VN-Pad5)") (class "Default")
      (node (ref "U3") (pin "5") (pinfunction "SENSOR_VN_5") (pintype "input"))
    )
    (net (code "78") (name "unconnected-(U4-CBUS0-Pad18)") (class "Default")
      (node (ref "U4") (pin "18") (pinfunction "CBUS0_18") (pintype "bidirectional"))
    )
    (net (code "79") (name "unconnected-(U4-CBUS1-Pad17)") (class "Default")
      (node (ref "U4") (pin "17") (pinfunction "CBUS1_17") (pintype "bidirectional"))
    )
    (net (code "80") (name "unconnected-(U4-CBUS2-Pad10)") (class "Default")
      (node (ref "U4") (pin "10") (pinfunction "CBUS2_10") (pintype "bidirectional"))
    )
    (net (code "81") (name "unconnected-(U4-CBUS3-Pad19)") (class "Default")
      (node (ref "U4") (pin "19") (pinfunction "CBUS3_19") (pintype "bidirectional"))
    )
    (net (code "82") (name "unconnected-(U4-~{CTS}-Pad9)") (class "Default")
      (node (ref "U4") (pin "9") (pinfunction "~{CTS}_9") (pintype "bidirectional"))
    )
    (net (code "83") (name "unconnected-(U4-~{DCD}-Pad8)") (class "Default")
      (node (ref "U4") (pin "8") (pinfunction "~{DCD}_8") (pintype "bidirectional"))
    )
    (net (code "84") (name "unconnected-(U4-~{DSR}-Pad7)") (class "Default")
      (node (ref "U4") (pin "7") (pinfunction "~{DSR}_7") (pintype "bidirectional"))
    )
    (net (code "85") (name "unconnected-(U4-~{RI}-Pad5)") (class "Default")
      (node (ref "U4") (pin "5") (pinfunction "~{RI}_5") (pintype "bidirectional"))
    )
  )
)
